# LilyGo-LoRa32.net
KiCad netlist of a schematic drawn in EasyEDA
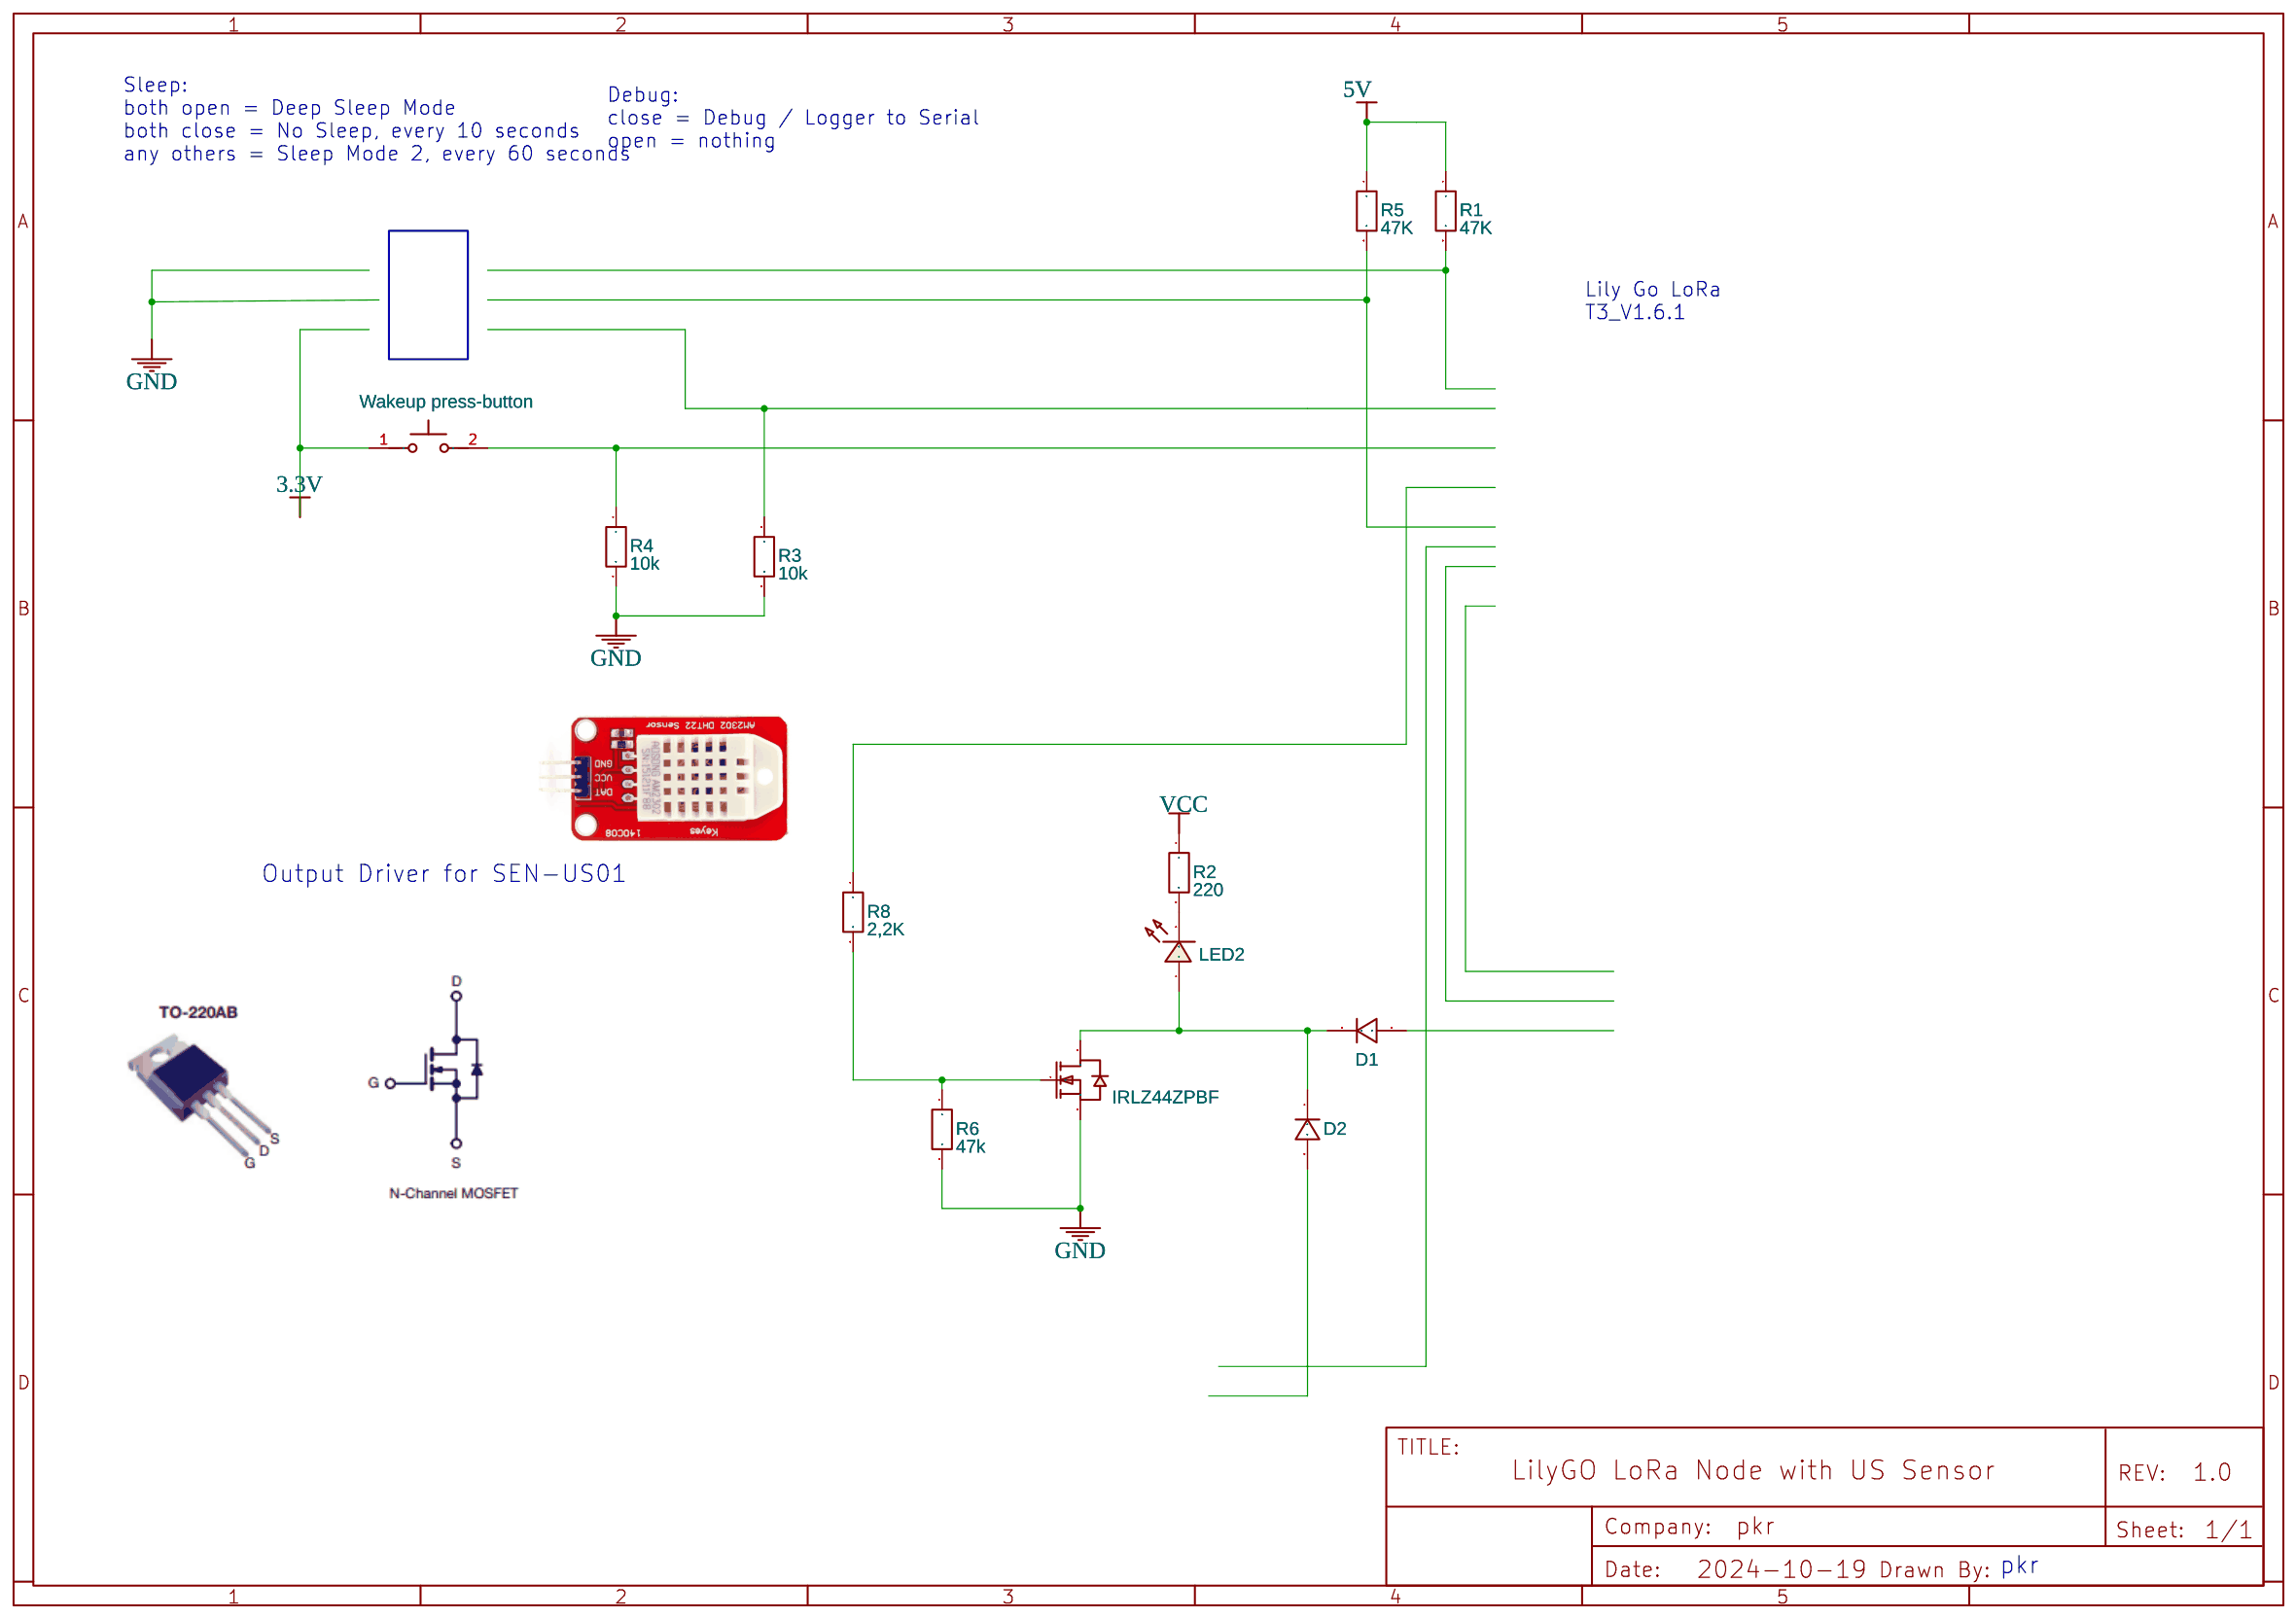
[diagram p0: schematic sheet]

(export (version "E")
  (design (tool "Eeschema 10.0.6"))
  (components
    (comp (ref "D1")
      (value "1N4007W")
      (fields (field (name "Manufacturer") "BLUE ROCKET"))
      (libsource (lib "") (part "1N4007W_1"))
    )
    (comp (ref "D2")
      (value "1N4007W")
      (fields (field (name "Manufacturer") "BLUE ROCKET"))
      (libsource (lib "") (part "1N4007W"))
    )
    (comp (ref "LED2")
      (value "LED-0603_R")
      (fields
        (field (name "Manufacturer Part") "19-217/R6C-AL1M2VY/3T")
        (field (name "Manufacturer") "EVERLIGHT(台湾亿光)")
      )
      (libsource (lib "") (part "LED-0603_R"))
    )
    (comp (ref "Q2")
      (value "IRLZ44ZPBF")
      (fields (field (name "Manufacturer") "Infineon(英飞凌)"))
      (libsource (lib "") (part "IRLZ44ZPBF"))
    )
    (comp (ref "R1") (value "47K") (libsource (lib "") (part "R_0603_EU")))
    (comp (ref "R2") (value "220") (libsource (lib "") (part "R_0603_EU")))
    (comp (ref "R3") (value "10k") (libsource (lib "") (part "R_0603_EU")))
    (comp (ref "R4") (value "10k") (libsource (lib "") (part "R_0603_EU")))
    (comp (ref "R5") (value "47K") (libsource (lib "") (part "R_0603_EU")))
    (comp (ref "R6") (value "47k") (libsource (lib "") (part "R_0603_EU")))
    (comp (ref "R8") (value "2,2K") (libsource (lib "") (part "R_0603_EU")))
    (comp (ref "SW1")
      (value "Wakeup press-button")
      (fields (field (name "Manufacturer Part") "CPG1511F01S05") (field (name "Manufacturer") "Kailh(凯华)"))
      (libsource (lib "") (part "CPG1511F01S05"))
    )
  )
  (nets
    (net (code "1") (name "3.3V") (class "Default")
      (node (ref "SW1") (pin "1") (pinfunction "1_1") (pintype "unspecified"))
    )
    (net (code "2") (name "5V") (class "Default")
      (node (ref "R1") (pin "1") (pinfunction "1_1") (pintype "unspecified"))
      (node (ref "R5") (pin "1") (pinfunction "1_1") (pintype "unspecified"))
    )
    (net (code "3") (name "GND") (class "Default")
      (node (ref "Q2") (pin "3") (pinfunction "S_3") (pintype "unspecified"))
      (node (ref "R3") (pin "2") (pinfunction "2_2") (pintype "unspecified"))
      (node (ref "R4") (pin "2") (pinfunction "2_2") (pintype "unspecified"))
      (node (ref "R6") (pin "2") (pinfunction "2_2") (pintype "unspecified"))
    )
    (net (code "4") (name "Net-(LED2-Pad2)") (class "Default")
      (node (ref "LED2") (pin "2") (pinfunction "2_2") (pintype "unspecified"))
      (node (ref "R2") (pin "2") (pinfunction "2_2") (pintype "unspecified"))
    )
    (net (code "5") (name "Net-(Q2-D)") (class "Default")
      (node (ref "D1") (pin "1") (pinfunction "1_1") (pintype "unspecified"))
      (node (ref "D2") (pin "1") (pinfunction "1_1") (pintype "unspecified"))
      (node (ref "LED2") (pin "1") (pinfunction "1_1") (pintype "unspecified"))
      (node (ref "Q2") (pin "2") (pinfunction "D_2") (pintype "unspecified"))
    )
    (net (code "6") (name "Net-(Q2-G)") (class "Default")
      (node (ref "Q2") (pin "1") (pinfunction "G_1") (pintype "unspecified"))
      (node (ref "R6") (pin "1") (pinfunction "1_1") (pintype "unspecified"))
      (node (ref "R8") (pin "2") (pinfunction "2_2") (pintype "unspecified"))
    )
    (net (code "7") (name "Net-(R4-Pad1)") (class "Default")
      (node (ref "R4") (pin "1") (pinfunction "1_1") (pintype "unspecified"))
      (node (ref "SW1") (pin "2") (pinfunction "2_2") (pintype "unspecified"))
    )
    (net (code "8") (name "VCC") (class "Default")
      (node (ref "R2") (pin "1") (pinfunction "1_1") (pintype "unspecified"))
    )
    (net (code "9") (name "unconnected-(D1-Pad2)") (class "Default")
      (node (ref "D1") (pin "2") (pinfunction "2_2") (pintype "unspecified"))
    )
    (net (code "10") (name "unconnected-(D2-Pad2)") (class "Default")
      (node (ref "D2") (pin "2") (pinfunction "2_2") (pintype "unspecified"))
    )
    (net (code "11") (name "unconnected-(R1-Pad2)") (class "Default")
      (node (ref "R1") (pin "2") (pinfunction "2_2") (pintype "unspecified"))
    )
    (net (code "12") (name "unconnected-(R3-Pad1)") (class "Default")
      (node (ref "R3") (pin "1") (pinfunction "1_1") (pintype "unspecified"))
    )
    (net (code "13") (name "unconnected-(R5-Pad2)") (class "Default")
      (node (ref "R5") (pin "2") (pinfunction "2_2") (pintype "unspecified"))
    )
    (net (code "14") (name "unconnected-(R8-Pad1)") (class "Default")
      (node (ref "R8") (pin "1") (pinfunction "1_1") (pintype "unspecified"))
    )
  )
)
